# KW2CPU_PCB.net
KiCad netlist of a schematic drawn in EAGLE
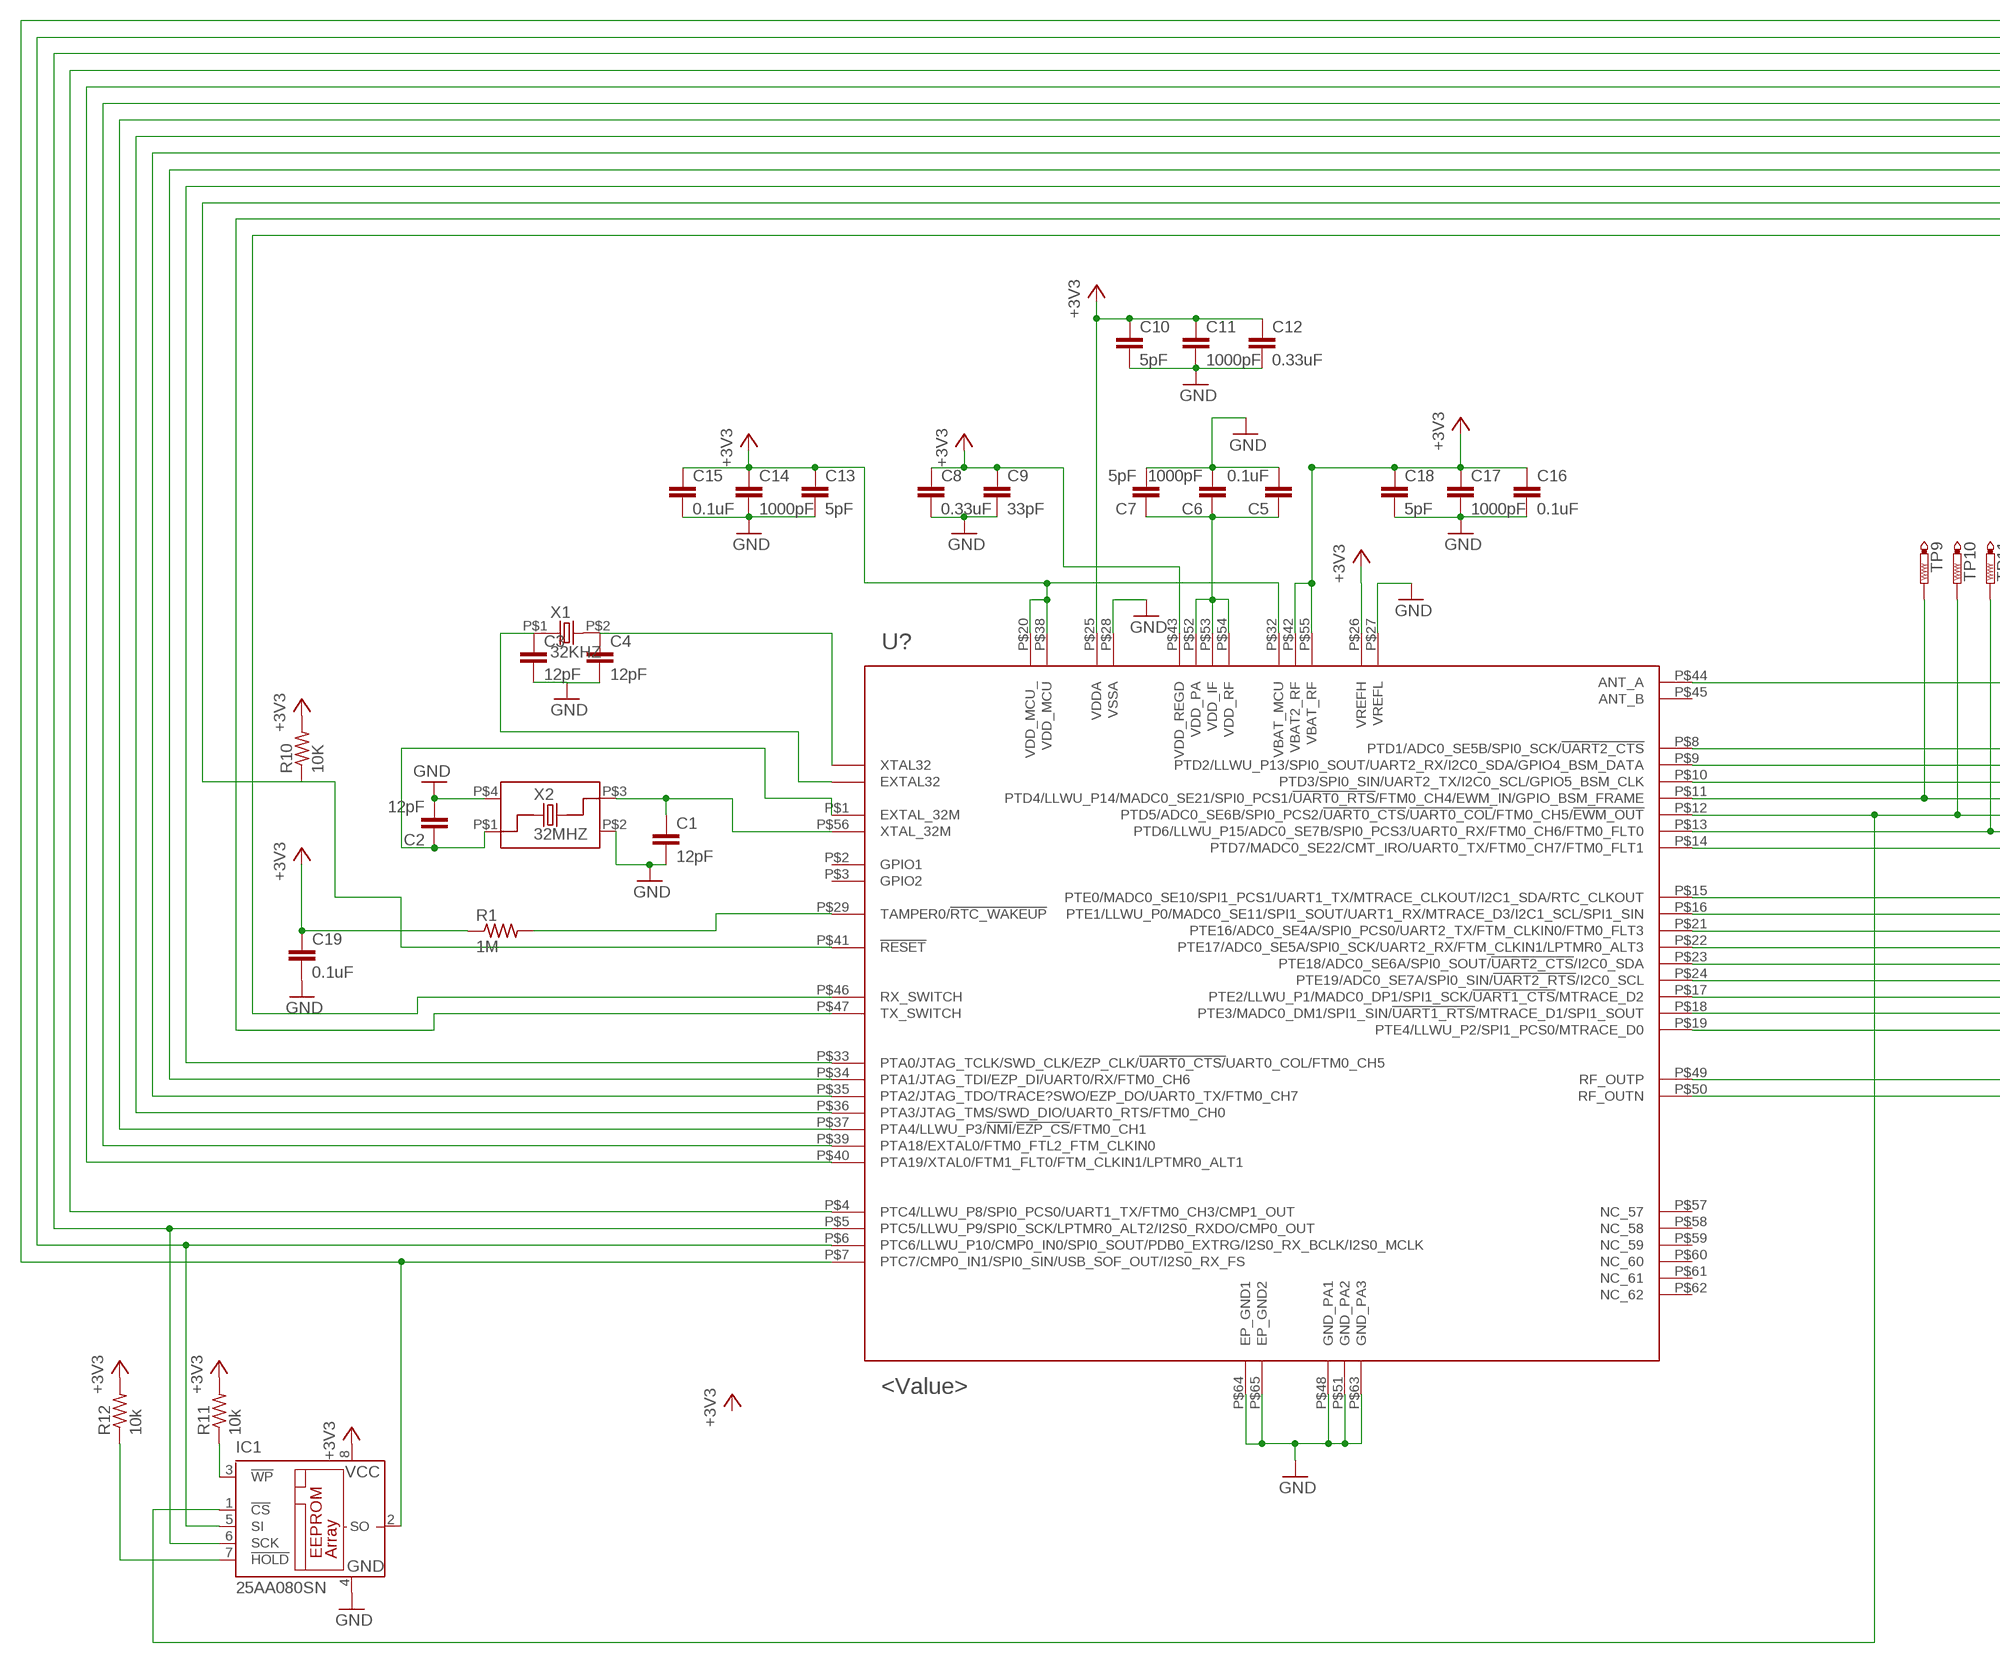
[diagram p0: schematic, sheet 1, part 1 of 2]
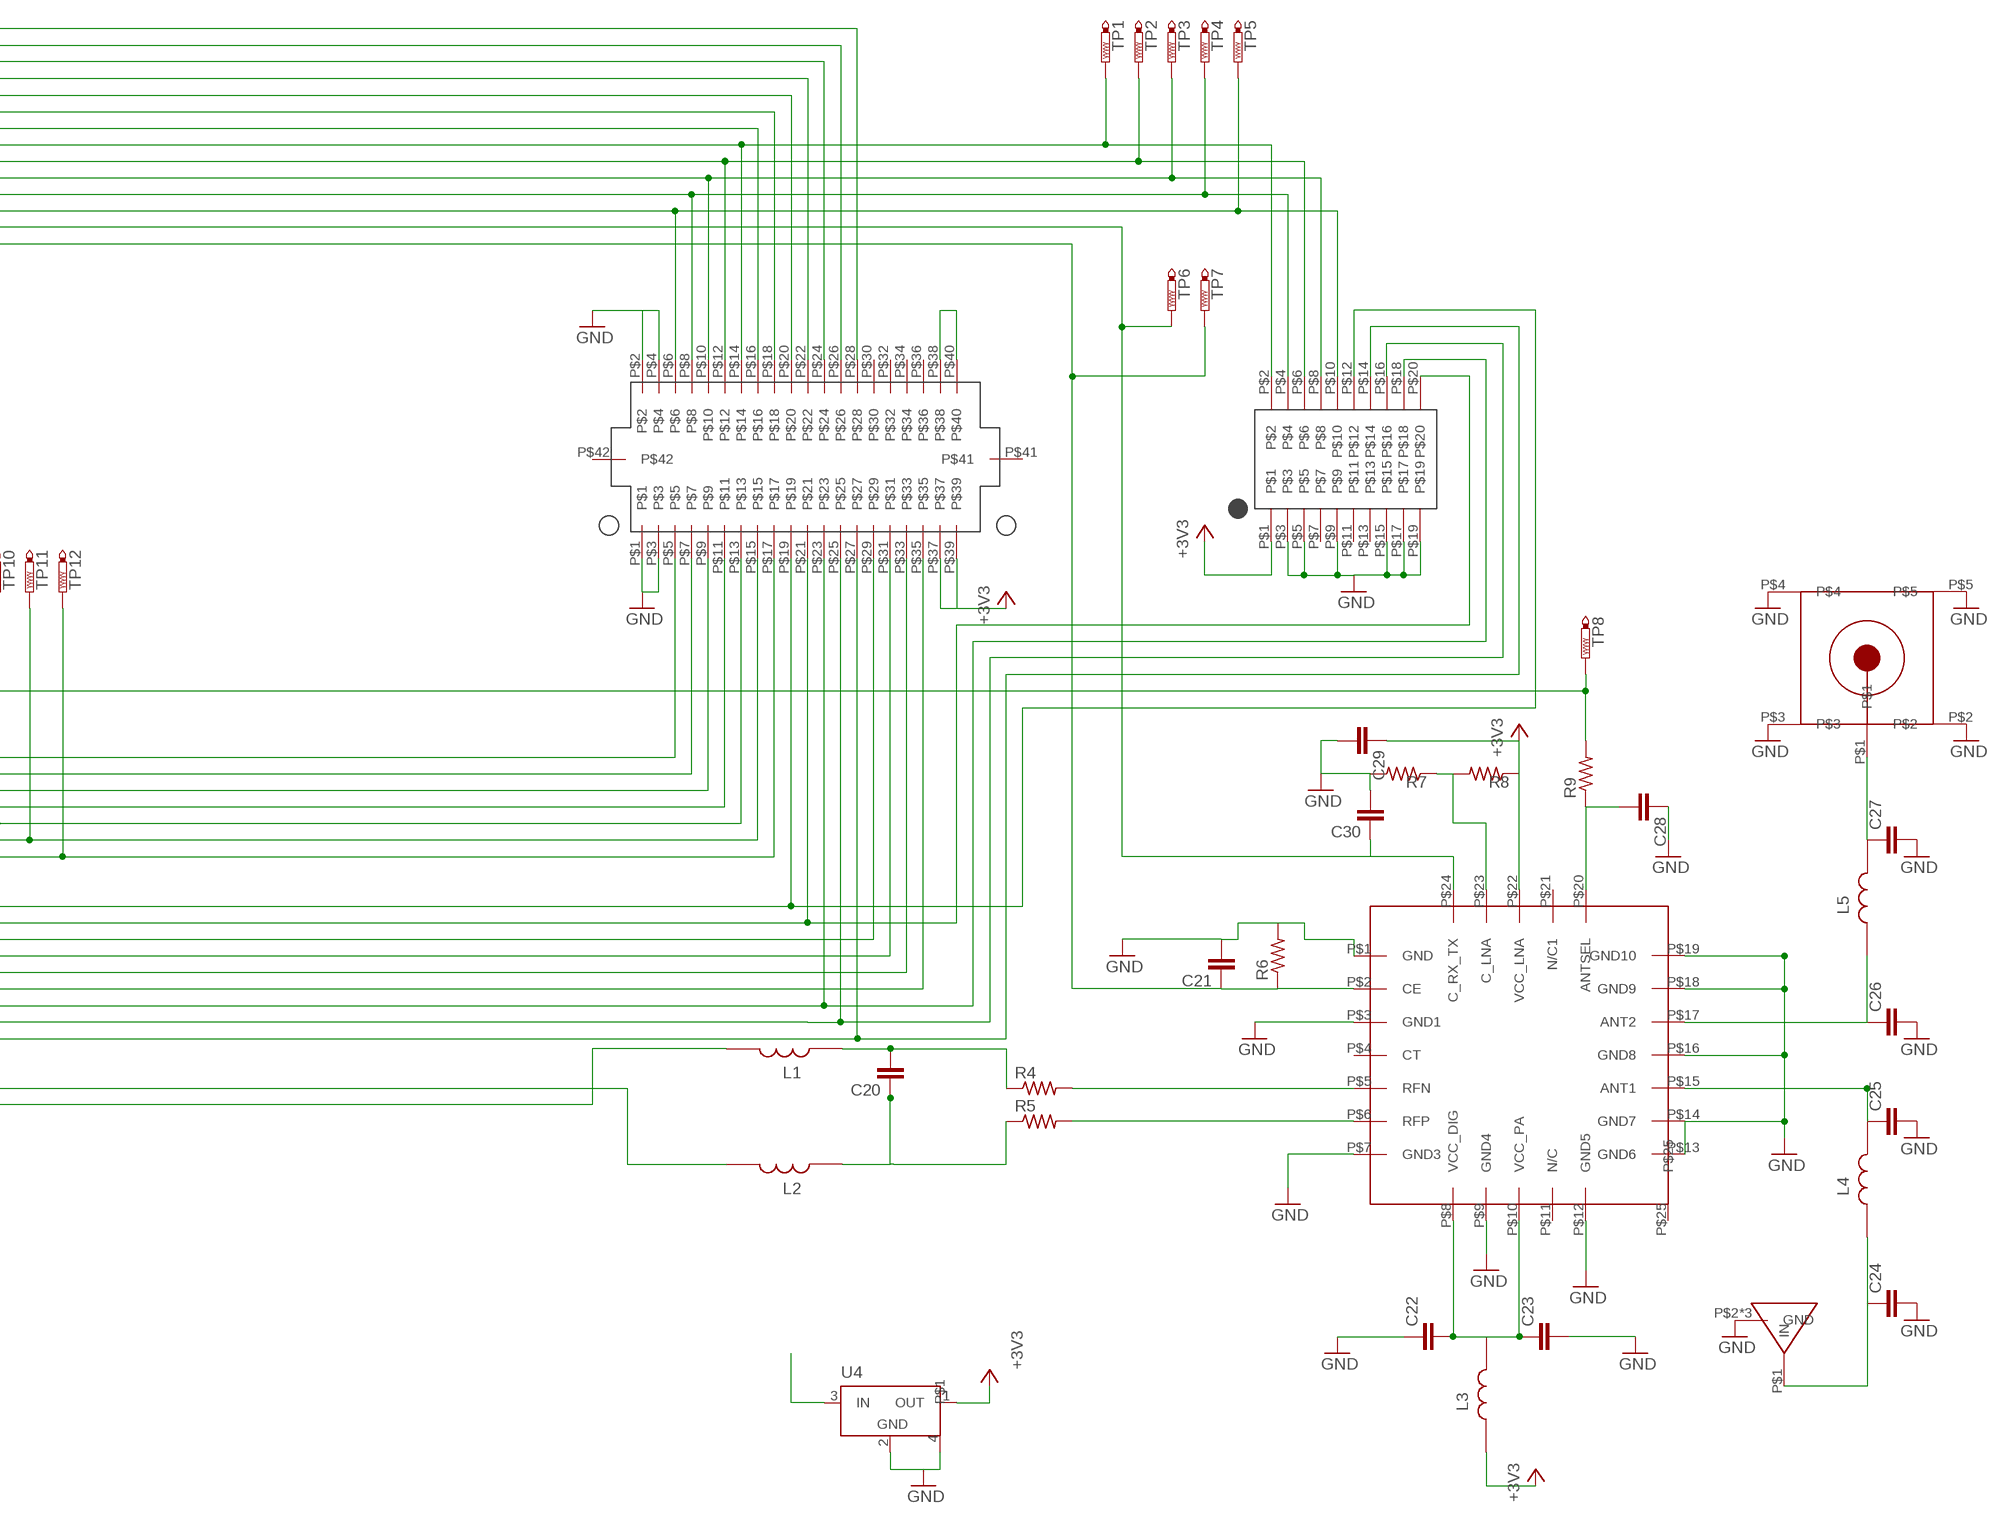
[diagram p1: schematic, sheet 1, part 2 of 2]

(export (version "E")
  (design (tool "Eeschema 10.0.6"))
  (components
    (comp (ref "C1")
      (value "12pF")
      (footprint "eagle-import:C0402")
      (libsource (lib "eagle-import") (part "RF-C0402"))
    )
    (comp (ref "C2")
      (value "12pF")
      (footprint "eagle-import:C0402")
      (libsource (lib "eagle-import") (part "RF-C0402"))
    )
    (comp (ref "C3")
      (value "12pF")
      (footprint "eagle-import:C0402")
      (libsource (lib "eagle-import") (part "RF-C0402"))
    )
    (comp (ref "C4")
      (value "12pF")
      (footprint "eagle-import:C0402")
      (libsource (lib "eagle-import") (part "RF-C0402"))
    )
    (comp (ref "C5")
      (value "0.1uF")
      (footprint "eagle-import:C0402")
      (libsource (lib "eagle-import") (part "RF-C0402"))
    )
    (comp (ref "C6")
      (value "1000pF")
      (footprint "eagle-import:C0402")
      (libsource (lib "eagle-import") (part "RF-C0402"))
    )
    (comp (ref "C7")
      (value "5pF")
      (footprint "eagle-import:C0402")
      (libsource (lib "eagle-import") (part "RF-C0402"))
    )
    (comp (ref "C8")
      (value "0.33uF")
      (footprint "eagle-import:C0402")
      (libsource (lib "eagle-import") (part "RF-C0402"))
    )
    (comp (ref "C9")
      (value "33pF")
      (footprint "eagle-import:C0402")
      (libsource (lib "eagle-import") (part "RF-C0402"))
    )
    (comp (ref "C10")
      (value "5pF")
      (footprint "eagle-import:C0402")
      (libsource (lib "eagle-import") (part "RF-C0402"))
    )
    (comp (ref "C11")
      (value "1000pF")
      (footprint "eagle-import:C0402")
      (libsource (lib "eagle-import") (part "RF-C0402"))
    )
    (comp (ref "C12")
      (value "0.33uF")
      (footprint "eagle-import:C0402")
      (libsource (lib "eagle-import") (part "RF-C0402"))
    )
    (comp (ref "C13")
      (value "5pF")
      (footprint "eagle-import:C0402")
      (libsource (lib "eagle-import") (part "RF-C0402"))
    )
    (comp (ref "C14")
      (value "1000pF")
      (footprint "eagle-import:C0402")
      (libsource (lib "eagle-import") (part "RF-C0402"))
    )
    (comp (ref "C15")
      (value "0.1uF")
      (footprint "eagle-import:C0402")
      (libsource (lib "eagle-import") (part "RF-C0402"))
    )
    (comp (ref "C16")
      (value "0.1uF")
      (footprint "eagle-import:C0402")
      (libsource (lib "eagle-import") (part "RF-C0402"))
    )
    (comp (ref "C17")
      (value "1000pF")
      (footprint "eagle-import:C0402")
      (libsource (lib "eagle-import") (part "RF-C0402"))
    )
    (comp (ref "C18")
      (value "5pF")
      (footprint "eagle-import:C0402")
      (libsource (lib "eagle-import") (part "RF-C0402"))
    )
    (comp (ref "C19")
      (value "0.1uF")
      (footprint "eagle-import:C0402")
      (libsource (lib "eagle-import") (part "RF-C0402"))
    )
    (comp (ref "C20")
      (value "RF-C")
      (footprint "eagle-import:RF-L0201")
      (libsource (lib "eagle-import") (part "RF-C"))
    )
    (comp (ref "C21")
      (value "RF-CRFMD")
      (footprint "eagle-import:RFMD0402")
      (libsource (lib "eagle-import") (part "RF-CRFMD"))
    )
    (comp (ref "C22")
      (value "RF-C")
      (footprint "eagle-import:RF-L0201")
      (libsource (lib "eagle-import") (part "RF-C"))
    )
    (comp (ref "C23")
      (value "RF-C")
      (footprint "eagle-import:RF-L0201")
      (libsource (lib "eagle-import") (part "RF-C"))
    )
    (comp (ref "C24")
      (value "RF-CRFMD")
      (footprint "eagle-import:RFMD0402")
      (libsource (lib "eagle-import") (part "RF-CRFMD"))
    )
    (comp (ref "C25")
      (value "RF-CRFMD")
      (footprint "eagle-import:RFMD0402")
      (libsource (lib "eagle-import") (part "RF-CRFMD"))
    )
    (comp (ref "C26")
      (value "RF-CRFMD")
      (footprint "eagle-import:RFMD0402")
      (libsource (lib "eagle-import") (part "RF-CRFMD"))
    )
    (comp (ref "C27")
      (value "RF-CRFMD")
      (footprint "eagle-import:RFMD0402")
      (libsource (lib "eagle-import") (part "RF-CRFMD"))
    )
    (comp (ref "C28")
      (value "RF-CRFMD")
      (footprint "eagle-import:RFMD0402")
      (libsource (lib "eagle-import") (part "RF-CRFMD"))
    )
    (comp (ref "C29")
      (value "RF-CRFMD")
      (footprint "eagle-import:RFMD0402")
      (libsource (lib "eagle-import") (part "RF-CRFMD"))
    )
    (comp (ref "C30")
      (value "RF-CRFMD")
      (footprint "eagle-import:RFMD0402")
      (libsource (lib "eagle-import") (part "RF-CRFMD"))
    )
    (comp (ref "IC1")
      (value "25AA080SN")
      (footprint "eagle-import:SO-08")
      (fields (field (name "MF") "MICROCHIP") (field (name "MPN") "25AA080/SN"))
      (libsource (lib "eagle-import") (part "25SNAA080"))
    )
    (comp (ref "J1")
      (value "DF12_M")
      (footprint "eagle-import:DF12_M")
      (libsource (lib "eagle-import") (part "DF12_M"))
    )
    (comp (ref "J2")
      (value "MOLEX55560-0207")
      (footprint "eagle-import:MOLEX55560-0207")
      (libsource (lib "eagle-import") (part "MOLEX55560-0207"))
    )
    (comp (ref "J3")
      (value "MMCX_VERT")
      (footprint "eagle-import:MMCX_VERT")
      (libsource (lib "eagle-import") (part "MMCX_VERT"))
    )
    (comp (ref "L1")
      (value "RF-L0201")
      (footprint "eagle-import:RF-L0201")
      (libsource (lib "eagle-import") (part "RF-L0201"))
    )
    (comp (ref "L2")
      (value "RF-L0201")
      (footprint "eagle-import:RF-L0201")
      (libsource (lib "eagle-import") (part "RF-L0201"))
    )
    (comp (ref "L3")
      (value "RF-L")
      (footprint "eagle-import:RFMD0402")
      (libsource (lib "eagle-import") (part "RF-L"))
    )
    (comp (ref "L4")
      (value "RF-L")
      (footprint "eagle-import:RFMD0402")
      (libsource (lib "eagle-import") (part "RF-L"))
    )
    (comp (ref "L5")
      (value "RF-L")
      (footprint "eagle-import:RFMD0402")
      (libsource (lib "eagle-import") (part "RF-L"))
    )
    (comp (ref "R1")
      (value "1M")
      (footprint "eagle-import:RF-R0402")
      (libsource (lib "eagle-import") (part "RF-R0402"))
    )
    (comp (ref "R4")
      (value "RF-R")
      (footprint "eagle-import:RF-L0201")
      (libsource (lib "eagle-import") (part "RF-R"))
    )
    (comp (ref "R5")
      (value "RF-R")
      (footprint "eagle-import:RF-L0201")
      (libsource (lib "eagle-import") (part "RF-R"))
    )
    (comp (ref "R6")
      (value "RF-RRFMD")
      (footprint "eagle-import:RFMD0402")
      (libsource (lib "eagle-import") (part "RF-RRFMD"))
    )
    (comp (ref "R7")
      (value "RF-RRFMD")
      (footprint "eagle-import:RFMD0402")
      (libsource (lib "eagle-import") (part "RF-RRFMD"))
    )
    (comp (ref "R8")
      (value "RF-RRFMD")
      (footprint "eagle-import:RFMD0402")
      (libsource (lib "eagle-import") (part "RF-RRFMD"))
    )
    (comp (ref "R9")
      (value "RF-RRFMD")
      (footprint "eagle-import:RFMD0402")
      (libsource (lib "eagle-import") (part "RF-RRFMD"))
    )
    (comp (ref "R10")
      (value "10K")
      (footprint "eagle-import:RF-R0402")
      (libsource (lib "eagle-import") (part "RF-R0402"))
    )
    (comp (ref "R11")
      (value "10k")
      (footprint "eagle-import:RF-R0402")
      (libsource (lib "eagle-import") (part "RF-R0402"))
    )
    (comp (ref "R12")
      (value "10k")
      (footprint "eagle-import:RF-R0402")
      (libsource (lib "eagle-import") (part "RF-R0402"))
    )
    (comp (ref "TP1")
      (value "PTR1TP15R")
      (footprint "eagle-import:TP15R")
      (libsource (lib "eagle-import") (part "PTR1TP15R"))
    )
    (comp (ref "TP2")
      (value "PTR1TP15R")
      (footprint "eagle-import:TP15R")
      (libsource (lib "eagle-import") (part "PTR1TP15R"))
    )
    (comp (ref "TP3")
      (value "PTR1TP15R")
      (footprint "eagle-import:TP15R")
      (libsource (lib "eagle-import") (part "PTR1TP15R"))
    )
    (comp (ref "TP4")
      (value "PTR1TP15R")
      (footprint "eagle-import:TP15R")
      (libsource (lib "eagle-import") (part "PTR1TP15R"))
    )
    (comp (ref "TP5")
      (value "PTR1TP15R")
      (footprint "eagle-import:TP15R")
      (libsource (lib "eagle-import") (part "PTR1TP15R"))
    )
    (comp (ref "TP6")
      (value "PTR1TP15R")
      (footprint "eagle-import:TP15R")
      (libsource (lib "eagle-import") (part "PTR1TP15R"))
    )
    (comp (ref "TP7")
      (value "PTR1TP15R")
      (footprint "eagle-import:TP15R")
      (libsource (lib "eagle-import") (part "PTR1TP15R"))
    )
    (comp (ref "TP8")
      (value "PTR1TP15R")
      (footprint "eagle-import:TP15R")
      (libsource (lib "eagle-import") (part "PTR1TP15R"))
    )
    (comp (ref "TP9")
      (value "PTR1TP15R")
      (footprint "eagle-import:TP15R")
      (libsource (lib "eagle-import") (part "PTR1TP15R"))
    )
    (comp (ref "TP10")
      (value "PTR1TP15R")
      (footprint "eagle-import:TP15R")
      (libsource (lib "eagle-import") (part "PTR1TP15R"))
    )
    (comp (ref "TP11")
      (value "PTR1TP15R")
      (footprint "eagle-import:TP15R")
      (libsource (lib "eagle-import") (part "PTR1TP15R"))
    )
    (comp (ref "TP12")
      (value "PTR1TP15R")
      (footprint "eagle-import:TP15R")
      (libsource (lib "eagle-import") (part "PTR1TP15R"))
    )
    (comp (ref "U1")
      (value "MKW21D")
      (footprint "eagle-import:LGA63")
      (libsource (lib "eagle-import") (part "MKW21D"))
    )
    (comp (ref "U3")
      (value "RF6555")
      (footprint "eagle-import:RF6555")
      (libsource (lib "eagle-import") (part "RF6555"))
    )
    (comp (ref "U4")
      (value "MCP1804T-3302I")
      (footprint "eagle-import:SOT223")
      (libsource (lib "eagle-import") (part "MCP1804T-3302I"))
    )
    (comp (ref "U5")
      (value "F-ANTENNA")
      (footprint "eagle-import:F_ANT_RFMD")
      (libsource (lib "eagle-import") (part "F-ANTENNA"))
    )
    (comp (ref "X1")
      (value "32KHZ")
      (footprint "eagle-import:32KHZSMD")
      (libsource (lib "eagle-import") (part "32KHZ"))
    )
    (comp (ref "X2")
      (value "32MHZ")
      (footprint "eagle-import:32MHZSMD")
      (libsource (lib "eagle-import") (part "32MHZ"))
    )
  )
  (nets
    (net (code "1") (name "+3V3") (class "Default")
      (node (ref "C10") (pin "1") (pinfunction "1_1") (pintype "passive"))
      (node (ref "C11") (pin "1") (pinfunction "1_1") (pintype "passive"))
      (node (ref "C12") (pin "1") (pinfunction "1_1") (pintype "passive"))
      (node (ref "C13") (pin "1") (pinfunction "1_1") (pintype "passive"))
      (node (ref "C14") (pin "1") (pinfunction "1_1") (pintype "passive"))
      (node (ref "C15") (pin "1") (pinfunction "1_1") (pintype "passive"))
      (node (ref "C16") (pin "1") (pinfunction "1_1") (pintype "passive"))
      (node (ref "C17") (pin "1") (pinfunction "1_1") (pintype "passive"))
      (node (ref "C18") (pin "1") (pinfunction "1_1") (pintype "passive"))
      (node (ref "C19") (pin "1") (pinfunction "1_1") (pintype "passive"))
      (node (ref "C29") (pin "P$1") (pinfunction "1_P$1") (pintype "passive"))
      (node (ref "C8") (pin "1") (pinfunction "1_1") (pintype "passive"))
      (node (ref "C9") (pin "1") (pinfunction "1_1") (pintype "passive"))
      (node (ref "IC1") (pin "8") (pinfunction "VCC_8") (pintype "power_in"))
      (node (ref "J1") (pin "P$37") (pinfunction "P$37_P$37") (pintype "bidirectional"))
      (node (ref "J1") (pin "P$39") (pinfunction "P$39_P$39") (pintype "bidirectional"))
      (node (ref "J2") (pin "P$1") (pinfunction "P$1_P$1") (pintype "bidirectional"))
      (node (ref "L3") (pin "P$2") (pinfunction "2_P$2") (pintype "bidirectional"))
      (node (ref "R1") (pin "1") (pinfunction "1_1") (pintype "passive"))
      (node (ref "R10") (pin "2") (pinfunction "2_2") (pintype "passive"))
      (node (ref "R11") (pin "2") (pinfunction "2_2") (pintype "passive"))
      (node (ref "R12") (pin "2") (pinfunction "2_2") (pintype "passive"))
      (node (ref "R8") (pin "P$1") (pinfunction "1_P$1") (pintype "passive"))
      (node (ref "U1") (pin "P$20") (pinfunction "VDD_MCU__P$20") (pintype "bidirectional"))
      (node (ref "U1") (pin "P$25") (pinfunction "VDDA_P$25") (pintype "bidirectional"))
      (node (ref "U1") (pin "P$26") (pinfunction "VREFH_P$26") (pintype "bidirectional"))
      (node (ref "U1") (pin "P$32") (pinfunction "VBAT_MCU_P$32") (pintype "bidirectional"))
      (node (ref "U1") (pin "P$38") (pinfunction "VDD_MCU_P$38") (pintype "bidirectional"))
      (node (ref "U1") (pin "P$42") (pinfunction "VBAT2_RF_P$42") (pintype "bidirectional"))
      (node (ref "U1") (pin "P$43") (pinfunction "VDD_REGD_P$43") (pintype "bidirectional"))
      (node (ref "U1") (pin "P$55") (pinfunction "VBAT_RF_P$55") (pintype "bidirectional"))
      (node (ref "U3") (pin "P$22") (pinfunction "VCC_LNA_P$22") (pintype "bidirectional"))
      (node (ref "U4") (pin "1") (pinfunction "OUT_1") (pintype "output"))
    )
    (net (code "2") (name "/VIN") (class "Default")
      (node (ref "J1") (pin "P$38") (pinfunction "P$38_P$38") (pintype "bidirectional"))
      (node (ref "J1") (pin "P$40") (pinfunction "P$40_P$40") (pintype "bidirectional"))
      (node (ref "U4") (pin "3") (pinfunction "IN_3") (pintype "input"))
    )
    (net (code "3") (name "GND") (class "Default")
      (node (ref "C1") (pin "2") (pinfunction "2_2") (pintype "passive"))
      (node (ref "C10") (pin "2") (pinfunction "2_2") (pintype "passive"))
      (node (ref "C11") (pin "2") (pinfunction "2_2") (pintype "passive"))
      (node (ref "C12") (pin "2") (pinfunction "2_2") (pintype "passive"))
      (node (ref "C13") (pin "2") (pinfunction "2_2") (pintype "passive"))
      (node (ref "C14") (pin "2") (pinfunction "2_2") (pintype "passive"))
      (node (ref "C15") (pin "2") (pinfunction "2_2") (pintype "passive"))
      (node (ref "C16") (pin "2") (pinfunction "2_2") (pintype "passive"))
      (node (ref "C17") (pin "2") (pinfunction "2_2") (pintype "passive"))
      (node (ref "C18") (pin "2") (pinfunction "2_2") (pintype "passive"))
      (node (ref "C19") (pin "2") (pinfunction "2_2") (pintype "passive"))
      (node (ref "C2") (pin "2") (pinfunction "2_2") (pintype "passive"))
      (node (ref "C21") (pin "P$2") (pinfunction "2_P$2") (pintype "passive"))
      (node (ref "C22") (pin "P$1") (pinfunction "1_P$1") (pintype "passive"))
      (node (ref "C23") (pin "P$2") (pinfunction "2_P$2") (pintype "passive"))
      (node (ref "C24") (pin "P$2") (pinfunction "2_P$2") (pintype "passive"))
      (node (ref "C25") (pin "P$2") (pinfunction "2_P$2") (pintype "passive"))
      (node (ref "C26") (pin "P$2") (pinfunction "2_P$2") (pintype "passive"))
      (node (ref "C27") (pin "P$2") (pinfunction "2_P$2") (pintype "passive"))
      (node (ref "C28") (pin "P$1") (pinfunction "1_P$1") (pintype "passive"))
      (node (ref "C29") (pin "P$2") (pinfunction "2_P$2") (pintype "passive"))
      (node (ref "C3") (pin "2") (pinfunction "2_2") (pintype "passive"))
      (node (ref "C30") (pin "P$1") (pinfunction "1_P$1") (pintype "passive"))
      (node (ref "C4") (pin "2") (pinfunction "2_2") (pintype "passive"))
      (node (ref "C5") (pin "2") (pinfunction "2_2") (pintype "passive"))
      (node (ref "C6") (pin "2") (pinfunction "2_2") (pintype "passive"))
      (node (ref "C7") (pin "2") (pinfunction "2_2") (pintype "passive"))
      (node (ref "C8") (pin "2") (pinfunction "2_2") (pintype "passive"))
      (node (ref "C9") (pin "2") (pinfunction "2_2") (pintype "passive"))
      (node (ref "IC1") (pin "4") (pinfunction "GND_4") (pintype "power_in"))
      (node (ref "J1") (pin "P$1") (pinfunction "P$1_P$1") (pintype "bidirectional"))
      (node (ref "J1") (pin "P$2") (pinfunction "P$2_P$2") (pintype "bidirectional"))
      (node (ref "J1") (pin "P$3") (pinfunction "P$3_P$3") (pintype "bidirectional"))
      (node (ref "J1") (pin "P$4") (pinfunction "P$4_P$4") (pintype "bidirectional"))
      (node (ref "J2") (pin "P$15") (pinfunction "P$15_P$15") (pintype "bidirectional"))
      (node (ref "J2") (pin "P$17") (pinfunction "P$17_P$17") (pintype "bidirectional"))
      (node (ref "J2") (pin "P$19") (pinfunction "P$19_P$19") (pintype "bidirectional"))
      (node (ref "J2") (pin "P$3") (pinfunction "P$3_P$3") (pintype "bidirectional"))
      (node (ref "J2") (pin "P$5") (pinfunction "P$5_P$5") (pintype "bidirectional"))
      (node (ref "J2") (pin "P$9") (pinfunction "P$9_P$9") (pintype "bidirectional"))
      (node (ref "J3") (pin "P$2") (pinfunction "P$2_P$2") (pintype "bidirectional"))
      (node (ref "J3") (pin "P$3") (pinfunction "P$3_P$3") (pintype "bidirectional"))
      (node (ref "J3") (pin "P$4") (pinfunction "P$4_P$4") (pintype "bidirectional"))
      (node (ref "J3") (pin "P$5") (pinfunction "P$5_P$5") (pintype "bidirectional"))
      (node (ref "R6") (pin "P$2") (pinfunction "2_P$2") (pintype "passive"))
      (node (ref "R7") (pin "P$2") (pinfunction "2_P$2") (pintype "passive"))
      (node (ref "U1") (pin "P$27") (pinfunction "VREFL_P$27") (pintype "bidirectional"))
      (node (ref "U1") (pin "P$28") (pinfunction "VSSA_P$28") (pintype "bidirectional"))
      (node (ref "U1") (pin "P$48") (pinfunction "GND_PA1_P$48") (pintype "bidirectional"))
      (node (ref "U1") (pin "P$51") (pinfunction "GND_PA2_P$51") (pintype "bidirectional"))
      (node (ref "U1") (pin "P$63") (pinfunction "GND_PA3_P$63") (pintype "bidirectional"))
      (node (ref "U1") (pin "P$64") (pinfunction "EP_GND1_P$64") (pintype "bidirectional"))
      (node (ref "U1") (pin "P$65") (pinfunction "EP_GND2_P$65") (pintype "bidirectional"))
      (node (ref "U3") (pin "P$1") (pinfunction "GND_P$1") (pintype "bidirectional"))
      (node (ref "U3") (pin "P$12") (pinfunction "GND5_P$12") (pintype "bidirectional"))
      (node (ref "U3") (pin "P$13") (pinfunction "GND6_P$13") (pintype "bidirectional"))
      (node (ref "U3") (pin "P$14") (pinfunction "GND7_P$14") (pintype "bidirectional"))
      (node (ref "U3") (pin "P$16") (pinfunction "GND8_P$16") (pintype "bidirectional"))
      (node (ref "U3") (pin "P$18") (pinfunction "GND9_P$18") (pintype "bidirectional"))
      (node (ref "U3") (pin "P$19") (pinfunction "GND10_P$19") (pintype "bidirectional"))
      (node (ref "U3") (pin "P$3") (pinfunction "GND1_P$3") (pintype "bidirectional"))
      (node (ref "U3") (pin "P$7") (pinfunction "GND3_P$7") (pintype "bidirectional"))
      (node (ref "U3") (pin "P$9") (pinfunction "GND4_P$9") (pintype "bidirectional"))
      (node (ref "U4") (pin "2") (pinfunction "GND_2") (pintype "power_in"))
      (node (ref "U4") (pin "4") (pinfunction "P$1_4") (pintype "bidirectional"))
      (node (ref "U5") (pin "P$2") (pinfunction "GND_P$2") (pintype "bidirectional"))
      (node (ref "U5") (pin "P$3") (pinfunction "GND_P$3") (pintype "bidirectional"))
      (node (ref "U5") (pin "P$4") (pinfunction "GND_P$4") (pintype "bidirectional"))
      (node (ref "X2") (pin "P$2") (pinfunction "P$2_P$2") (pintype "power_in"))
      (node (ref "X2") (pin "P$4") (pinfunction "P$4_P$4") (pintype "bidirectional"))
    )
    (net (code "4") (name "Net-(C20-1)") (class "Default")
      (node (ref "C20") (pin "P$1") (pinfunction "1_P$1") (pintype "passive"))
      (node (ref "L2") (pin "P$2") (pinfunction "2_P$2") (pintype "bidirectional"))
      (node (ref "R5") (pin "P$1") (pinfunction "1_P$1") (pintype "passive"))
    )
    (net (code "5") (name "Net-(C20-2)") (class "Default")
      (node (ref "C20") (pin "P$2") (pinfunction "2_P$2") (pintype "passive"))
      (node (ref "L1") (pin "P$2") (pinfunction "2_P$2") (pintype "bidirectional"))
      (node (ref "R4") (pin "P$1") (pinfunction "1_P$1") (pintype "passive"))
    )
    (net (code "6") (name "Net-(C21-1)") (class "Default")
      (node (ref "C21") (pin "P$1") (pinfunction "1_P$1") (pintype "passive"))
      (node (ref "R6") (pin "P$1") (pinfunction "1_P$1") (pintype "passive"))
      (node (ref "TP7") (pin "TP") (pinfunction "TP_TP") (pintype "input"))
      (node (ref "U1") (pin "P$46") (pinfunction "RX_SWITCH_P$46") (pintype "bidirectional"))
      (node (ref "U3") (pin "P$2") (pinfunction "CE_P$2") (pintype "bidirectional"))
    )
    (net (code "7") (name "Net-(C22-2)") (class "Default")
      (node (ref "C22") (pin "P$2") (pinfunction "2_P$2") (pintype "passive"))
      (node (ref "C23") (pin "P$1") (pinfunction "1_P$1") (pintype "passive"))
      (node (ref "L3") (pin "P$1") (pinfunction "1_P$1") (pintype "bidirectional"))
      (node (ref "U3") (pin "P$10") (pinfunction "VCC_PA_P$10") (pintype "bidirectional"))
      (node (ref "U3") (pin "P$8") (pinfunction "VCC_DIG_P$8") (pintype "bidirectional"))
    )
    (net (code "8") (name "Net-(C24-1)") (class "Default")
      (node (ref "C24") (pin "P$1") (pinfunction "1_P$1") (pintype "passive"))
      (node (ref "L4") (pin "P$2") (pinfunction "2_P$2") (pintype "bidirectional"))
      (node (ref "U5") (pin "P$1") (pinfunction "IN_P$1") (pintype "bidirectional"))
    )
    (net (code "9") (name "Net-(C25-1)") (class "Default")
      (node (ref "C25") (pin "P$1") (pinfunction "1_P$1") (pintype "passive"))
      (node (ref "L4") (pin "P$1") (pinfunction "1_P$1") (pintype "bidirectional"))
      (node (ref "U3") (pin "P$15") (pinfunction "ANT1_P$15") (pintype "bidirectional"))
    )
    (net (code "10") (name "Net-(C26-1)") (class "Default")
      (node (ref "C26") (pin "P$1") (pinfunction "1_P$1") (pintype "passive"))
      (node (ref "L5") (pin "P$2") (pinfunction "2_P$2") (pintype "bidirectional"))
      (node (ref "U3") (pin "P$17") (pinfunction "ANT2_P$17") (pintype "bidirectional"))
    )
    (net (code "11") (name "Net-(C27-1)") (class "Default")
      (node (ref "C27") (pin "P$1") (pinfunction "1_P$1") (pintype "passive"))
      (node (ref "J3") (pin "P$1") (pinfunction "P$1_P$1") (pintype "bidirectional"))
      (node (ref "L5") (pin "P$1") (pinfunction "1_P$1") (pintype "bidirectional"))
    )
    (net (code "12") (name "Net-(C28-2)") (class "Default")
      (node (ref "C28") (pin "P$2") (pinfunction "2_P$2") (pintype "passive"))
      (node (ref "R9") (pin "P$1") (pinfunction "1_P$1") (pintype "passive"))
      (node (ref "U3") (pin "P$20") (pinfunction "ANTSEL_P$20") (pintype "bidirectional"))
    )
    (net (code "13") (name "Net-(C30-2)") (class "Default")
      (node (ref "C30") (pin "P$2") (pinfunction "2_P$2") (pintype "passive"))
      (node (ref "TP6") (pin "TP") (pinfunction "TP_TP") (pintype "input"))
      (node (ref "U1") (pin "P$47") (pinfunction "TX_SWITCH_P$47") (pintype "bidirectional"))
      (node (ref "U3") (pin "P$24") (pinfunction "C_RX_TX_P$24") (pintype "bidirectional"))
    )
    (net (code "14") (name "Net-(IC1-SCK)") (class "Default")
      (node (ref "IC1") (pin "6") (pinfunction "SCK_6") (pintype "input"))
      (node (ref "J1") (pin "P$24") (pinfunction "P$24_P$24") (pintype "bidirectional"))
      (node (ref "U1") (pin "P$5") (pinfunction "PTC5/LLWU_P9/SPI0_SCK/LPTMR0_ALT2/I2S0_RXDO/CMP0_OUT_P$5") (pintype "bidirectional"))
    )
    (net (code "15") (name "Net-(IC1-SI)") (class "Default")
      (node (ref "IC1") (pin "5") (pinfunction "SI_5") (pintype "input"))
      (node (ref "J1") (pin "P$26") (pinfunction "P$26_P$26") (pintype "bidirectional"))
      (node (ref "U1") (pin "P$6") (pinfunction "PTC6/LLWU_P10/CMP0_IN0/SPI0_SOUT/PDB0_EXTRG/I2S0_RX_BCLK/I2S0_MCLK_P$6") (pintype "bidirectional"))
    )
    (net (code "16") (name "Net-(IC1-SO)") (class "Default")
      (node (ref "IC1") (pin "2") (pinfunction "SO_2") (pintype "bidirectional"))
      (node (ref "J1") (pin "P$28") (pinfunction "P$28_P$28") (pintype "bidirectional"))
      (node (ref "U1") (pin "P$7") (pinfunction "PTC7/CMP0_IN1/SPI0_SIN/USB_SOF_OUT/I2S0_RX_FS_P$7") (pintype "bidirectional"))
    )
    (net (code "17") (name "Net-(IC1-~{CS})") (class "Default")
      (node (ref "IC1") (pin "1") (pinfunction "~{CS}_1") (pintype "input"))
      (node (ref "J1") (pin "P$13") (pinfunction "P$13_P$13") (pintype "bidirectional"))
      (node (ref "TP10") (pin "TP") (pinfunction "TP_TP") (pintype "input"))
      (node (ref "U1") (pin "P$12") (pinfunction "PTD5/ADC0_SE6B/SPI0_PCS2/~{UART0_CTS}/~{UART0_COL}/FTM0_CH5/~{EWM_OUT}_P$12") (pintype "bidirectional"))
    )
    (net (code "18") (name "Net-(IC1-~{HOLD})") (class "Default")
      (node (ref "IC1") (pin "7") (pinfunction "~{HOLD}_7") (pintype "input"))
      (node (ref "R12") (pin "1") (pinfunction "1_1") (pintype "passive"))
    )
    (net (code "19") (name "Net-(IC1-~{WP})") (class "Default")
      (node (ref "IC1") (pin "3") (pinfunction "~{WP}_3") (pintype "input"))
      (node (ref "R11") (pin "1") (pinfunction "1_1") (pintype "passive"))
    )
    (net (code "20") (name "Net-(L1-1)") (class "Default")
      (node (ref "L1") (pin "P$1") (pinfunction "1_P$1") (pintype "bidirectional"))
      (node (ref "U1") (pin "P$50") (pinfunction "RF_OUTN_P$50") (pintype "bidirectional"))
    )
    (net (code "21") (name "Net-(L2-1)") (class "Default")
      (node (ref "L2") (pin "P$1") (pinfunction "1_P$1") (pintype "bidirectional"))
      (node (ref "U1") (pin "P$49") (pinfunction "RF_OUTP_P$49") (pintype "bidirectional"))
    )
    (net (code "22") (name "Net-(R4-2)") (class "Default")
      (node (ref "R4") (pin "P$2") (pinfunction "2_P$2") (pintype "passive"))
      (node (ref "U3") (pin "P$5") (pinfunction "RFN_P$5") (pintype "bidirectional"))
    )
    (net (code "23") (name "Net-(R5-2)") (class "Default")
      (node (ref "R5") (pin "P$2") (pinfunction "2_P$2") (pintype "passive"))
      (node (ref "U3") (pin "P$6") (pinfunction "RFP_P$6") (pintype "bidirectional"))
    )
    (net (code "24") (name "Net-(R7-1)") (class "Default")
      (node (ref "R7") (pin "P$1") (pinfunction "1_P$1") (pintype "passive"))
      (node (ref "R8") (pin "P$2") (pinfunction "2_P$2") (pintype "passive"))
      (node (ref "U3") (pin "P$23") (pinfunction "C_LNA_P$23") (pintype "bidirectional"))
    )
    (net (code "25") (name "Net-(R9-2)") (class "Default")
      (node (ref "R9") (pin "P$2") (pinfunction "2_P$2") (pintype "passive"))
      (node (ref "TP8") (pin "TP") (pinfunction "TP_TP") (pintype "input"))
      (node (ref "U1") (pin "P$44") (pinfunction "ANT_A_P$44") (pintype "bidirectional"))
    )
    (net (code "26") (name "Net-(U1-EXTAL32)") (class "Default")
      (node (ref "C3") (pin "1") (pinfunction "1_1") (pintype "passive"))
      (node (ref "U1") (pin "P$31") (pinfunction "EXTAL32_P$31") (pintype "bidirectional"))
      (node (ref "X1") (pin "P$1") (pinfunction "1_P$1") (pintype "passive"))
    )
    (net (code "27") (name "Net-(U1-EXTAL_32M)") (class "Default")
      (node (ref "C2") (pin "1") (pinfunction "1_1") (pintype "passive"))
      (node (ref "U1") (pin "P$1") (pinfunction "EXTAL_32M_P$1") (pintype "bidirectional"))
      (node (ref "X2") (pin "P$1") (pinfunction "P$1_P$1") (pintype "passive"))
    )
    (net (code "28") (name "Net-(U1-PTA0{slash}JTAG_TCLK{slash}SWD_CLK{slash}EZP_CLK{slash}~{UART0_CTS{slash}}UART0_COL{slash}FTM0_CH5)") (class "Default")
      (node (ref "J1") (pin "P$8") (pinfunction "P$8_P$8") (pintype "bidirectional"))
      (node (ref "J2") (pin "P$4") (pinfunction "P$4_P$4") (pintype "bidirectional"))
      (node (ref "TP4") (pin "TP") (pinfunction "TP_TP") (pintype "input"))
      (node (ref "U1") (pin "P$33") (pinfunction "PTA0/JTAG_TCLK/SWD_CLK/EZP_CLK/~{UART0_CTS/}UART0_COL/FTM0_CH5_P$33") (pintype "bidirectional"))
    )
    (net (code "29") (name "Net-(U1-PTA1{slash}JTAG_TDI{slash}EZP_DI{slash}UART0{slash}RX{slash}FTM0_CH6)") (class "Default")
      (node (ref "J1") (pin "P$10") (pinfunction "P$10_P$10") (pintype "bidirectional"))
      (node (ref "J2") (pin "P$8") (pinfunction "P$8_P$8") (pintype "bidirectional"))
      (node (ref "TP3") (pin "TP") (pinfunction "TP_TP") (pintype "input"))
      (node (ref "U1") (pin "P$34") (pinfunction "PTA1/JTAG_TDI/EZP_DI/UART0/RX/FTM0_CH6_P$34") (pintype "bidirectional"))
    )
    (net (code "30") (name "Net-(U1-PTA2{slash}JTAG_TDO{slash}TRACE?SWO{slash}EZP_DO{slash}UART0_TX{slash}FTM0_CH7)") (class "Default")
      (node (ref "J1") (pin "P$12") (pinfunction "P$12_P$12") (pintype "bidirectional"))
      (node (ref "J2") (pin "P$6") (pinfunction "P$6_P$6") (pintype "bidirectional"))
      (node (ref "TP2") (pin "TP") (pinfunction "TP_TP") (pintype "input"))
      (node (ref "U1") (pin "P$35") (pinfunction "PTA2/JTAG_TDO/TRACE?SWO/EZP_DO/UART0_TX/FTM0_CH7_P$35") (pintype "bidirectional"))
    )
    (net (code "31") (name "Net-(U1-PTA3{slash}JTAG_TMS{slash}SWD_DIO{slash}UART0_RTS{slash}FTM0_CH0)") (class "Default")
      (node (ref "J1") (pin "P$14") (pinfunction "P$14_P$14") (pintype "bidirectional"))
      (node (ref "J2") (pin "P$2") (pinfunction "P$2_P$2") (pintype "bidirectional"))
      (node (ref "TP1") (pin "TP") (pinfunction "TP_TP") (pintype "input"))
      (node (ref "U1") (pin "P$36") (pinfunction "PTA3/JTAG_TMS/SWD_DIO/UART0_RTS/FTM0_CH0_P$36") (pintype "bidirectional"))
    )
    (net (code "32") (name "Net-(U1-PTA4{slash}LLWU_P3{slash}~{NMI}{slash}~{EZP_CS}{slash}FTM0_CH1)") (class "Default")
      (node (ref "J1") (pin "P$16") (pinfunction "P$16_P$16") (pintype "bidirectional"))
      (node (ref "U1") (pin "P$37") (pinfunction "PTA4/LLWU_P3/~{NMI}/~{EZP_CS}/FTM0_CH1_P$37") (pintype "bidirectional"))
    )
    (net (code "33") (name "Net-(U1-PTA18{slash}EXTAL0{slash}FTM0_FTL2_FTM_CLKIN0)") (class "Default")
      (node (ref "J1") (pin "P$18") (pinfunction "P$18_P$18") (pintype "bidirectional"))
      (node (ref "U1") (pin "P$39") (pinfunction "PTA18/EXTAL0/FTM0_FTL2_FTM_CLKIN0_P$39") (pintype "bidirectional"))
    )
    (net (code "34") (name "Net-(U1-PTA19{slash}XTAL0{slash}FTM1_FLT0{slash}FTM_CLKIN1{slash}LPTMR0_ALT1)") (class "Default")
      (node (ref "J1") (pin "P$20") (pinfunction "P$20_P$20") (pintype "bidirectional"))
      (node (ref "U1") (pin "P$40") (pinfunction "PTA19/XTAL0/FTM1_FLT0/FTM_CLKIN1/LPTMR0_ALT1_P$40") (pintype "bidirectional"))
    )
    (net (code "35") (name "Net-(U1-PTC4{slash}LLWU_P8{slash}SPI0_PCS0{slash}UART1_TX{slash}FTM0_CH3{slash}CMP1_OUT)") (class "Default")
      (node (ref "J1") (pin "P$22") (pinfunction "P$22_P$22") (pintype "bidirectional"))
      (node (ref "U1") (pin "P$4") (pinfunction "PTC4/LLWU_P8/SPI0_PCS0/UART1_TX/FTM0_CH3/CMP1_OUT_P$4") (pintype "bidirectional"))
    )
    (net (code "36") (name "Net-(U1-PTD1{slash}ADC0_SE5B{slash}SPI0_SCK{slash}~{UART2_CTS})") (class "Default")
      (node (ref "J1") (pin "P$5") (pinfunction "P$5_P$5") (pintype "bidirectional"))
      (node (ref "U1") (pin "P$8") (pinfunction "PTD1/ADC0_SE5B/SPI0_SCK/~{UART2_CTS}_P$8") (pintype "bidirectional"))
    )
    (net (code "37") (name "Net-(U1-PTD2{slash}LLWU_P13{slash}SPI0_SOUT{slash}UART2_RX{slash}I2C0_SDA{slash}GPIO4_BSM_DATA)") (class "Default")
      (node (ref "J1") (pin "P$7") (pinfunction "P$7_P$7") (pintype "bidirectional"))
      (node (ref "U1") (pin "P$9") (pinfunction "PTD2/LLWU_P13/SPI0_SOUT/UART2_RX/I2C0_SDA/GPIO4_BSM_DATA_P$9") (pintype "bidirectional"))
    )
    (net (code "38") (name "Net-(U1-PTD3{slash}SPI0_SIN{slash}UART2_TX{slash}I2C0_SCL{slash}GPIO5_BSM_CLK)") (class "Default")
      (node (ref "J1") (pin "P$9") (pinfunction "P$9_P$9") (pintype "bidirectional"))
      (node (ref "U1") (pin "P$10") (pinfunction "PTD3/SPI0_SIN/UART2_TX/I2C0_SCL/GPIO5_BSM_CLK_P$10") (pintype "bidirectional"))
    )
    (net (code "39") (name "Net-(U1-PTD4{slash}LLWU_P14{slash}MADC0_SE21{slash}SPI0_PCS1{slash}~{UART0_RTS}{slash}FTM0_CH4{slash}EWM_IN{slash}GPIO_BSM_FRAME)") (class "Default")
      (node (ref "J1") (pin "P$11") (pinfunction "P$11_P$11") (pintype "bidirectional"))
      (node (ref "TP9") (pin "TP") (pinfunction "TP_TP") (pintype "input"))
      (node (ref "U1") (pin "P$11") (pinfunction "PTD4/LLWU_P14/MADC0_SE21/SPI0_PCS1/~{UART0_RTS}/FTM0_CH4/EWM_IN/GPIO_BSM_FRAME_P$11") (pintype "bidirectional"))
    )
    (net (code "40") (name "Net-(U1-PTD6{slash}LLWU_P15{slash}ADC0_SE7B{slash}SPI0_PCS3{slash}UART0_RX{slash}FTM0_CH6{slash}FTM0_FLT0)") (class "Default")
      (node (ref "J1") (pin "P$15") (pinfunction "P$15_P$15") (pintype "bidirectional"))
      (node (ref "TP11") (pin "TP") (pinfunction "TP_TP") (pintype "input"))
      (node (ref "U1") (pin "P$13") (pinfunction "PTD6/LLWU_P15/ADC0_SE7B/SPI0_PCS3/UART0_RX/FTM0_CH6/FTM0_FLT0_P$13") (pintype "bidirectional"))
    )
    (net (code "41") (name "Net-(U1-PTD7{slash}MADC0_SE22{slash}CMT_IRO{slash}UART0_TX{slash}FTM0_CH7{slash}FTM0_FLT1)") (class "Default")
      (node (ref "J1") (pin "P$17") (pinfunction "P$17_P$17") (pintype "bidirectional"))
      (node (ref "TP12") (pin "TP") (pinfunction "TP_TP") (pintype "input"))
      (node (ref "U1") (pin "P$14") (pinfunction "PTD7/MADC0_SE22/CMT_IRO/UART0_TX/FTM0_CH7/FTM0_FLT1_P$14") (pintype "bidirectional"))
    )
    (net (code "42") (name "Net-(U1-PTE0{slash}MADC0_SE10{slash}SPI1_PCS1{slash}UART1_TX{slash}MTRACE_CLKOUT{slash}I2C1_SDA{slash}RTC_CLKOUT)") (class "Default")
      (node (ref "J1") (pin "P$19") (pinfunction "P$19_P$19") (pintype "bidirectional"))
      (node (ref "J2") (pin "P$12") (pinfunction "P$12_P$12") (pintype "bidirectional"))
      (node (ref "U1") (pin "P$15") (pinfunction "PTE0/MADC0_SE10/SPI1_PCS1/UART1_TX/MTRACE_CLKOUT/I2C1_SDA/RTC_CLKOUT_P$15") (pintype "bidirectional"))
    )
    (net (code "43") (name "Net-(U1-PTE1{slash}LLWU_P0{slash}MADC0_SE11{slash}SPI1_SOUT{slash}UART1_RX{slash}MTRACE_D3{slash}I2C1_SCL{slash}SPI1_SIN)") (class "Default")
      (node (ref "J1") (pin "P$21") (pinfunction "P$21_P$21") (pintype "bidirectional"))
      (node (ref "J2") (pin "P$20") (pinfunction "P$20_P$20") (pintype "bidirectional"))
      (node (ref "U1") (pin "P$16") (pinfunction "PTE1/LLWU_P0/MADC0_SE11/SPI1_SOUT/UART1_RX/MTRACE_D3/I2C1_SCL/SPI1_SIN_P$16") (pintype "bidirectional"))
    )
    (net (code "44") (name "Net-(U1-PTE2{slash}LLWU_P1{slash}MADC0_DP1{slash}SPI1_SCK{slash}~{UART1_CTS}{slash}MTRACE_D2)") (class "Default")
      (node (ref "J1") (pin "P$23") (pinfunction "P$23_P$23") (pintype "bidirectional"))
      (node (ref "J2") (pin "P$18") (pinfunction "P$18_P$18") (pintype "bidirectional"))
      (node (ref "U1") (pin "P$17") (pinfunction "PTE2/LLWU_P1/MADC0_DP1/SPI1_SCK/~{UART1_CTS}/MTRACE_D2_P$17") (pintype "bidirectional"))
    )
    (net (code "45") (name "Net-(U1-PTE3{slash}MADC0_DM1{slash}SPI1_SIN{slash}~{UART1_RTS}{slash}MTRACE_D1{slash}SPI1_SOUT)") (class "Default")
      (node (ref "J1") (pin "P$25") (pinfunction "P$25_P$25") (pintype "bidirectional"))
      (node (ref "J2") (pin "P$16") (pinfunction "P$16_P$16") (pintype "bidirectional"))
      (node (ref "U1") (pin "P$18") (pinfunction "PTE3/MADC0_DM1/SPI1_SIN/~{UART1_RTS}/MTRACE_D1/SPI1_SOUT_P$18") (pintype "bidirectional"))
    )
    (net (code "46") (name "Net-(U1-PTE4{slash}LLWU_P2{slash}SPI1_PCS0{slash}MTRACE_D0)") (class "Default")
      (node (ref "J1") (pin "P$27") (pinfunction "P$27_P$27") (pintype "bidirectional"))
      (node (ref "J2") (pin "P$14") (pinfunction "P$14_P$14") (pintype "bidirectional"))
      (node (ref "U1") (pin "P$19") (pinfunction "PTE4/LLWU_P2/SPI1_PCS0/MTRACE_D0_P$19") (pintype "bidirectional"))
    )
    (net (code "47") (name "Net-(U1-PTE16{slash}ADC0_SE4A{slash}SPI0_PCS0{slash}UART2_TX{slash}FTM_CLKIN0{slash}FTM0_FLT3)") (class "Default")
      (node (ref "J1") (pin "P$29") (pinfunction "P$29_P$29") (pintype "bidirectional"))
      (node (ref "U1") (pin "P$21") (pinfunction "PTE16/ADC0_SE4A/SPI0_PCS0/UART2_TX/FTM_CLKIN0/FTM0_FLT3_P$21") (pintype "bidirectional"))
    )
    (net (code "48") (name "Net-(U1-PTE17{slash}ADC0_SE5A{slash}SPI0_SCK{slash}UART2_RX{slash}FTM_CLKIN1{slash}LPTMR0_ALT3)") (class "Default")
      (node (ref "J1") (pin "P$31") (pinfunction "P$31_P$31") (pintype "bidirectional"))
      (node (ref "U1") (pin "P$22") (pinfunction "PTE17/ADC0_SE5A/SPI0_SCK/UART2_RX/FTM_CLKIN1/LPTMR0_ALT3_P$22") (pintype "bidirectional"))
    )
    (net (code "49") (name "Net-(U1-PTE18{slash}ADC0_SE6A{slash}SPI0_SOUT{slash}~{UART2_CTS}{slash}I2C0_SDA)") (class "Default")
      (node (ref "J1") (pin "P$33") (pinfunction "P$33_P$33") (pintype "bidirectional"))
      (node (ref "U1") (pin "P$23") (pinfunction "PTE18/ADC0_SE6A/SPI0_SOUT/~{UART2_CTS}/I2C0_SDA_P$23") (pintype "bidirectional"))
    )
    (net (code "50") (name "Net-(U1-PTE19{slash}ADC0_SE7A{slash}SPI0_SIN{slash}~{UART2_RTS}{slash}I2C0_SCL)") (class "Default")
      (node (ref "J1") (pin "P$35") (pinfunction "P$35_P$35") (pintype "bidirectional"))
      (node (ref "U1") (pin "P$24") (pinfunction "PTE19/ADC0_SE7A/SPI0_SIN/~{UART2_RTS}/I2C0_SCL_P$24") (pintype "bidirectional"))
    )
    (net (code "51") (name "Net-(U1-TAMPER0{slash}~{RTC_WAKEUP})") (class "Default")
      (node (ref "R1") (pin "2") (pinfunction "2_2") (pintype "passive"))
      (node (ref "U1") (pin "P$29") (pinfunction "TAMPER0/~{RTC_WAKEUP}_P$29") (pintype "bidirectional"))
    )
    (net (code "52") (name "Net-(U1-VDD_IF)") (class "Default")
      (node (ref "C5") (pin "1") (pinfunction "1_1") (pintype "passive"))
      (node (ref "C6") (pin "1") (pinfunction "1_1") (pintype "passive"))
      (node (ref "C7") (pin "1") (pinfunction "1_1") (pintype "passive"))
      (node (ref "U1") (pin "P$52") (pinfunction "VDD_PA_P$52") (pintype "bidirectional"))
      (node (ref "U1") (pin "P$53") (pinfunction "VDD_IF_P$53") (pintype "bidirectional"))
      (node (ref "U1") (pin "P$54") (pinfunction "VDD_RF_P$54") (pintype "bidirectional"))
    )
    (net (code "53") (name "Net-(U1-XTAL32)") (class "Default")
      (node (ref "C4") (pin "1") (pinfunction "1_1") (pintype "passive"))
      (node (ref "U1") (pin "P$30") (pinfunction "XTAL32_P$30") (pintype "bidirectional"))
      (node (ref "X1") (pin "P$2") (pinfunction "2_P$2") (pintype "passive"))
    )
    (net (code "54") (name "Net-(U1-XTAL_32M)") (class "Default")
      (node (ref "C1") (pin "1") (pinfunction "1_1") (pintype "passive"))
      (node (ref "U1") (pin "P$56") (pinfunction "XTAL_32M_P$56") (pintype "bidirectional"))
      (node (ref "X2") (pin "P$3") (pinfunction "P$3_P$3") (pintype "passive"))
    )
    (net (code "55") (name "Net-(U1-~{RESET})") (class "Default")
      (node (ref "J1") (pin "P$6") (pinfunction "P$6_P$6") (pintype "bidirectional"))
      (node (ref "J2") (pin "P$10") (pinfunction "P$10_P$10") (pintype "bidirectional"))
      (node (ref "R10") (pin "1") (pinfunction "1_1") (pintype "passive"))
      (node (ref "TP5") (pin "TP") (pinfunction "TP_TP") (pintype "input"))
      (node (ref "U1") (pin "P$41") (pinfunction "~{RESET}_P$41") (pintype "bidirectional"))
    )
    (net (code "56") (name "unconnected-(J1-PadP$30)") (class "Default")
      (node (ref "J1") (pin "P$30") (pinfunction "P$30_P$30") (pintype "bidirectional"))
    )
    (net (code "57") (name "unconnected-(J1-PadP$32)") (class "Default")
      (node (ref "J1") (pin "P$32") (pinfunction "P$32_P$32") (pintype "bidirectional"))
    )
    (net (code "58") (name "unconnected-(J1-PadP$34)") (class "Default")
      (node (ref "J1") (pin "P$34") (pinfunction "P$34_P$34") (pintype "bidirectional"))
    )
    (net (code "59") (name "unconnected-(J1-PadP$36)") (class "Default")
      (node (ref "J1") (pin "P$36") (pinfunction "P$36_P$36") (pintype "bidirectional"))
    )
    (net (code "60") (name "unconnected-(J1-PadP$41)") (class "Default")
      (node (ref "J1") (pin "P$41") (pinfunction "P$41_P$41") (pintype "bidirectional"))
    )
    (net (code "61") (name "unconnected-(J1-PadP$42)") (class "Default")
      (node (ref "J1") (pin "P$42") (pinfunction "P$42_P$42") (pintype "bidirectional"))
    )
    (net (code "62") (name "unconnected-(J2-PadP$7)") (class "Default")
      (node (ref "J2") (pin "P$7") (pinfunction "P$7_P$7") (pintype "bidirectional"))
    )
    (net (code "63") (name "unconnected-(J2-PadP$11)") (class "Default")
      (node (ref "J2") (pin "P$11") (pinfunction "P$11_P$11") (pintype "bidirectional"))
    )
    (net (code "64") (name "unconnected-(J2-PadP$13)") (class "Default")
      (node (ref "J2") (pin "P$13") (pinfunction "P$13_P$13") (pintype "bidirectional"))
    )
    (net (code "65") (name "unconnected-(U1-ANT_B-PadP$45)") (class "Default")
      (node (ref "U1") (pin "P$45") (pinfunction "ANT_B_P$45") (pintype "bidirectional"))
    )
    (net (code "66") (name "unconnected-(U1-GPIO1-PadP$2)") (class "Default")
      (node (ref "U1") (pin "P$2") (pinfunction "GPIO1_P$2") (pintype "bidirectional"))
    )
    (net (code "67") (name "unconnected-(U1-GPIO2-PadP$3)") (class "Default")
      (node (ref "U1") (pin "P$3") (pinfunction "GPIO2_P$3") (pintype "bidirectional"))
    )
    (net (code "68") (name "unconnected-(U1-NC_57-PadP$57)") (class "Default")
      (node (ref "U1") (pin "P$57") (pinfunction "NC_57_P$57") (pintype "bidirectional"))
    )
    (net (code "69") (name "unconnected-(U1-NC_58-PadP$58)") (class "Default")
      (node (ref "U1") (pin "P$58") (pinfunction "NC_58_P$58") (pintype "bidirectional"))
    )
    (net (code "70") (name "unconnected-(U1-NC_59-PadP$59)") (class "Default")
      (node (ref "U1") (pin "P$59") (pinfunction "NC_59_P$59") (pintype "bidirectional"))
    )
    (net (code "71") (name "unconnected-(U1-NC_60-PadP$60)") (class "Default")
      (node (ref "U1") (pin "P$60") (pinfunction "NC_60_P$60") (pintype "bidirectional"))
    )
    (net (code "72") (name "unconnected-(U1-NC_61-PadP$61)") (class "Default")
      (node (ref "U1") (pin "P$61") (pinfunction "NC_61_P$61") (pintype "bidirectional"))
    )
    (net (code "73") (name "unconnected-(U1-NC_62-PadP$62)") (class "Default")
      (node (ref "U1") (pin "P$62") (pinfunction "NC_62_P$62") (pintype "bidirectional"))
    )
    (net (code "74") (name "unconnected-(U3-CT-PadP$4)") (class "Default")
      (node (ref "U3") (pin "P$4") (pinfunction "CT_P$4") (pintype "bidirectional"))
    )
    (net (code "75") (name "unconnected-(U3-N{slash}C-PadP$11)") (class "Default")
      (node (ref "U3") (pin "P$11") (pinfunction "N/C_P$11") (pintype "bidirectional"))
    )
    (net (code "76") (name "unconnected-(U3-N{slash}C1-PadP$21)") (class "Default")
      (node (ref "U3") (pin "P$21") (pinfunction "N/C1_P$21") (pintype "bidirectional"))
    )
    (net (code "77") (name "unconnected-(U3-PadP$25)") (class "Default")
      (node (ref "U3") (pin "P$25") (pinfunction "P$25_P$25") (pintype "bidirectional"))
    )
  )
)
